# 8PinPortConnectorOffset_v1.net
KiCad netlist of a schematic drawn in EAGLE
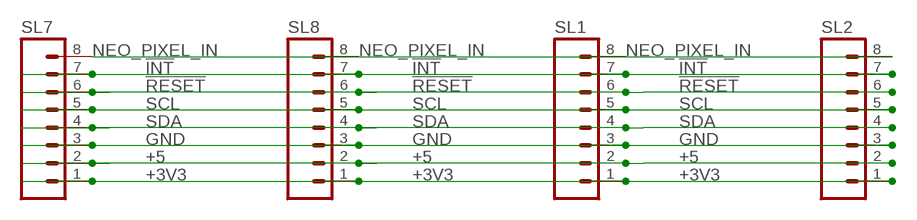
[diagram p0: schematic, sheet 1]

(export (version "E")
  (design (tool "Eeschema 10.0.6"))
  (components
    (comp (ref "SL1")
      (value "MA08")
      (footprint "eagle-import:08PA")
      (libsource (lib "eagle-import") (part "MA08"))
    )
    (comp (ref "SL2")
      (value "MA08")
      (footprint "eagle-import:08PA")
      (libsource (lib "eagle-import") (part "MA08"))
    )
    (comp (ref "SL7")
      (value "MA08")
      (footprint "eagle-import:08PA")
      (libsource (lib "eagle-import") (part "MA08"))
    )
    (comp (ref "SL8")
      (value "MA08")
      (footprint "eagle-import:08PA")
      (libsource (lib "eagle-import") (part "MA08"))
    )
  )
  (nets
    (net (code "1") (name "/+3V3") (class "Default")
      (node (ref "SL1") (pin "1") (pinfunction "1_1") (pintype "passive"))
      (node (ref "SL2") (pin "1") (pinfunction "1_1") (pintype "passive"))
      (node (ref "SL7") (pin "1") (pinfunction "1_1") (pintype "passive"))
      (node (ref "SL8") (pin "1") (pinfunction "1_1") (pintype "passive"))
    )
    (net (code "2") (name "/+5") (class "Default")
      (node (ref "SL1") (pin "2") (pinfunction "2_2") (pintype "passive"))
      (node (ref "SL2") (pin "2") (pinfunction "2_2") (pintype "passive"))
      (node (ref "SL7") (pin "2") (pinfunction "2_2") (pintype "passive"))
      (node (ref "SL8") (pin "2") (pinfunction "2_2") (pintype "passive"))
    )
    (net (code "3") (name "/GND") (class "Default")
      (node (ref "SL1") (pin "3") (pinfunction "3_3") (pintype "passive"))
      (node (ref "SL2") (pin "3") (pinfunction "3_3") (pintype "passive"))
      (node (ref "SL7") (pin "3") (pinfunction "3_3") (pintype "passive"))
      (node (ref "SL8") (pin "3") (pinfunction "3_3") (pintype "passive"))
    )
    (net (code "4") (name "/NEO_PIXEL_IN") (class "Default")
      (node (ref "SL1") (pin "8") (pinfunction "8_8") (pintype "passive"))
      (node (ref "SL2") (pin "8") (pinfunction "8_8") (pintype "passive"))
      (node (ref "SL7") (pin "8") (pinfunction "8_8") (pintype "passive"))
      (node (ref "SL8") (pin "8") (pinfunction "8_8") (pintype "passive"))
    )
    (net (code "5") (name "/SCL") (class "Default")
      (node (ref "SL1") (pin "5") (pinfunction "5_5") (pintype "passive"))
      (node (ref "SL2") (pin "5") (pinfunction "5_5") (pintype "passive"))
      (node (ref "SL7") (pin "5") (pinfunction "5_5") (pintype "passive"))
      (node (ref "SL8") (pin "5") (pinfunction "5_5") (pintype "passive"))
    )
    (net (code "6") (name "/SDA") (class "Default")
      (node (ref "SL1") (pin "4") (pinfunction "4_4") (pintype "passive"))
      (node (ref "SL2") (pin "4") (pinfunction "4_4") (pintype "passive"))
      (node (ref "SL7") (pin "4") (pinfunction "4_4") (pintype "passive"))
      (node (ref "SL8") (pin "4") (pinfunction "4_4") (pintype "passive"))
    )
    (net (code "7") (name "/~{INT}") (class "Default")
      (node (ref "SL1") (pin "7") (pinfunction "7_7") (pintype "passive"))
      (node (ref "SL2") (pin "7") (pinfunction "7_7") (pintype "passive"))
      (node (ref "SL7") (pin "7") (pinfunction "7_7") (pintype "passive"))
      (node (ref "SL8") (pin "7") (pinfunction "7_7") (pintype "passive"))
    )
    (net (code "8") (name "/~{RESET}") (class "Default")
      (node (ref "SL1") (pin "6") (pinfunction "6_6") (pintype "passive"))
      (node (ref "SL2") (pin "6") (pinfunction "6_6") (pintype "passive"))
      (node (ref "SL7") (pin "6") (pinfunction "6_6") (pintype "passive"))
      (node (ref "SL8") (pin "6") (pinfunction "6_6") (pintype "passive"))
    )
  )
)
